# 18650_1S3P_Smart_VertCon.net
KiCad netlist of a schematic drawn in EAGLE
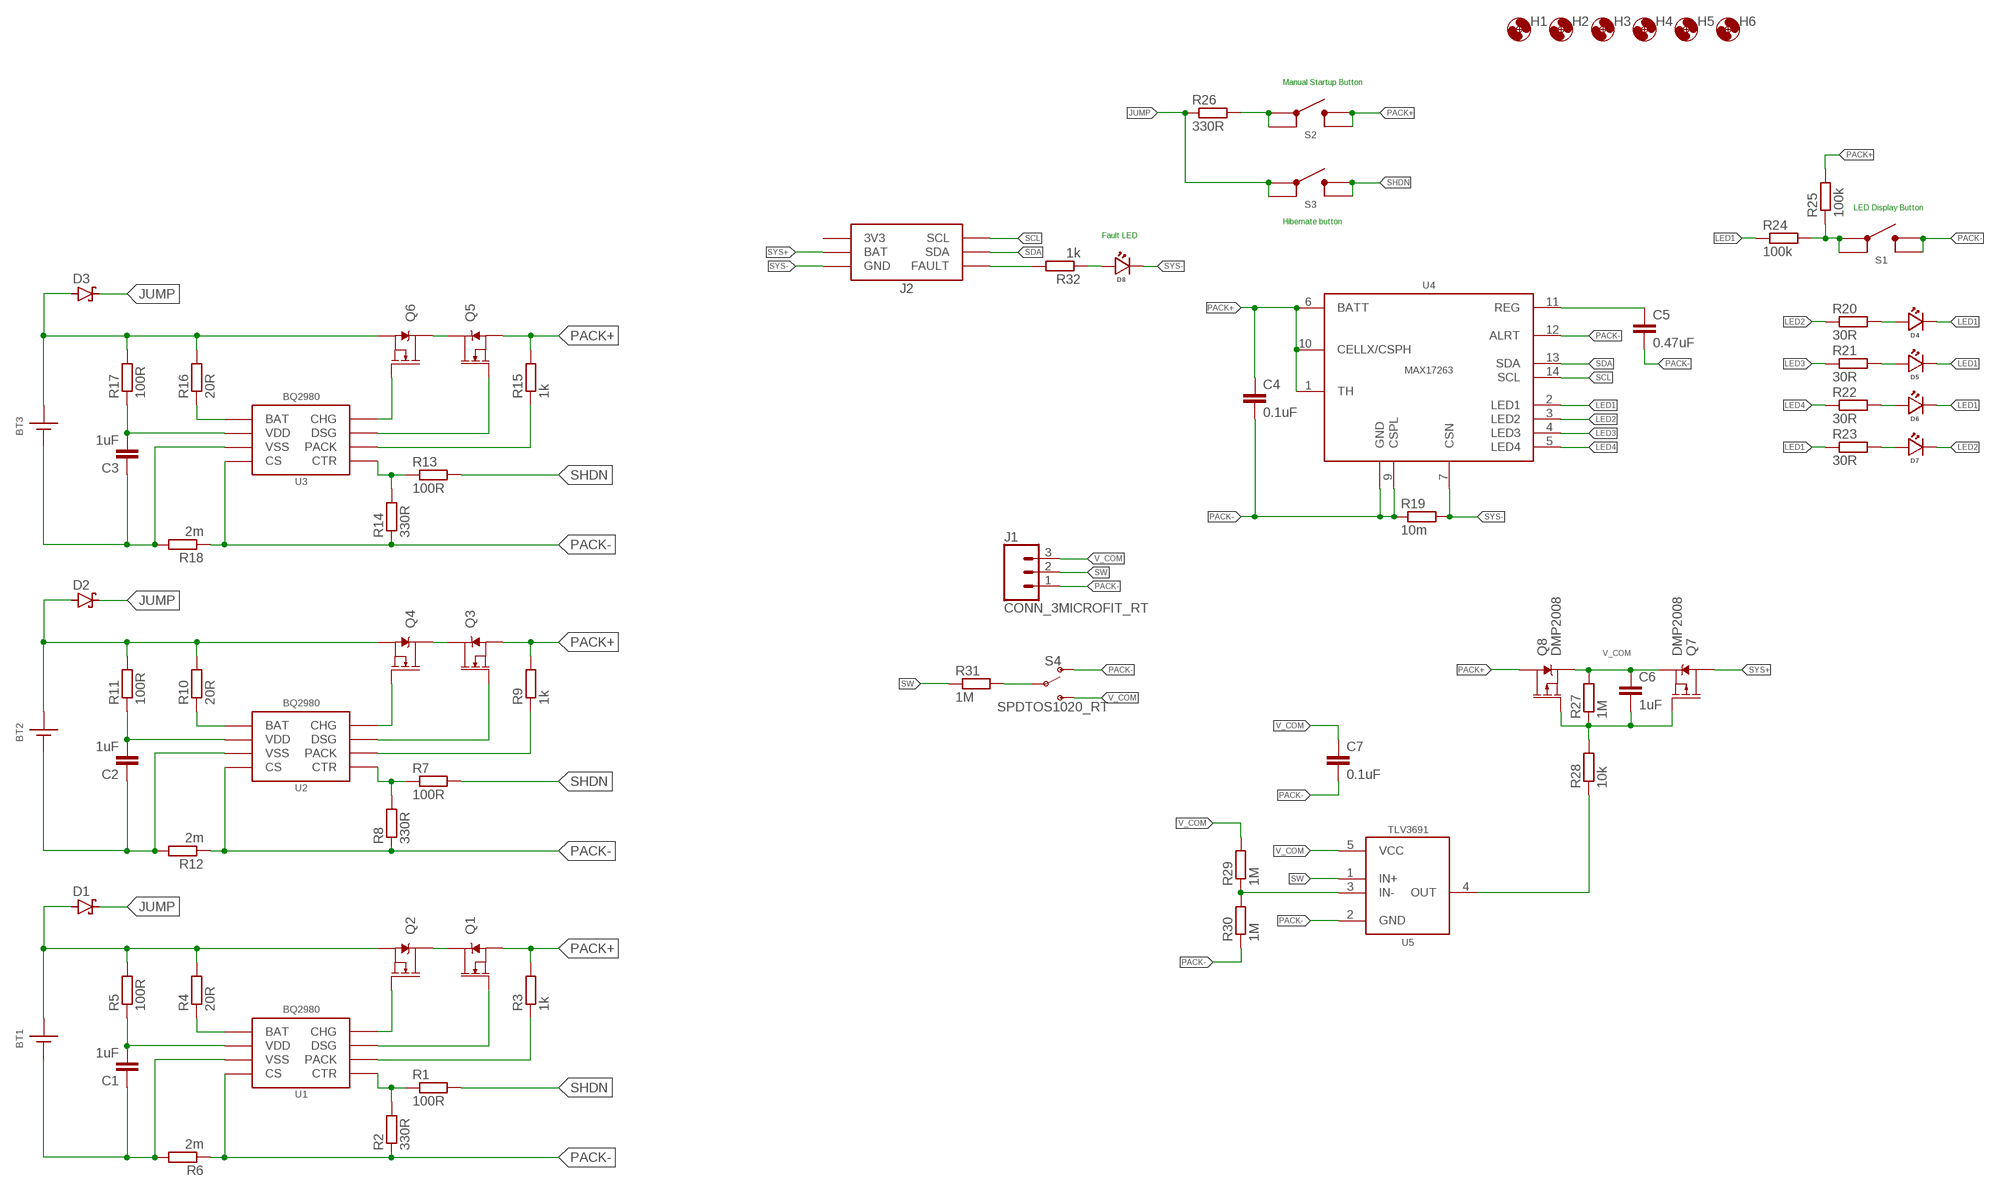
[diagram p0: schematic, sheet 1]

(export (version "E")
  (design (tool "Eeschema 10.0.6"))
  (components
    (comp (ref "BT1")
      (value "186501042")
      (footprint "eagle-import:BATT_1042P")
      (fields
        (field (name "MF") "Keystone")
        (field (name "MPN") "1042")
        (field (name "DIGIKEY") "36-1042-ND")
        (field (name "MPN_1") "1042")
      )
      (libsource (lib "eagle-import") (part "186501042"))
    )
    (comp (ref "BT2")
      (value "186501042")
      (footprint "eagle-import:BATT_1042P")
      (fields
        (field (name "MF") "Keystone")
        (field (name "MPN") "1042")
        (field (name "DIGIKEY") "36-1042-ND")
        (field (name "MPN_1") "1042")
      )
      (libsource (lib "eagle-import") (part "186501042"))
    )
    (comp (ref "BT3")
      (value "186501042")
      (footprint "eagle-import:BATT_1042P")
      (fields
        (field (name "MF") "Keystone")
        (field (name "MPN") "1042")
        (field (name "DIGIKEY") "36-1042-ND")
        (field (name "MPN_1") "1042")
      )
      (libsource (lib "eagle-import") (part "186501042"))
    )
    (comp (ref "C1")
      (value "1uF")
      (footprint "eagle-import:C0603")
      (fields (field (name "MF") "Yaiyo Yuden") (field (name "MPN") "TMK107B7105KA-T"))
      (libsource (lib "eagle-import") (part "C-EUC06031UF"))
    )
    (comp (ref "C2")
      (value "1uF")
      (footprint "eagle-import:C0603")
      (fields (field (name "MF") "Yaiyo Yuden") (field (name "MPN") "TMK107B7105KA-T"))
      (libsource (lib "eagle-import") (part "C-EUC06031UF"))
    )
    (comp (ref "C3")
      (value "1uF")
      (footprint "eagle-import:C0603")
      (fields (field (name "MF") "Yaiyo Yuden") (field (name "MPN") "TMK107B7105KA-T"))
      (libsource (lib "eagle-import") (part "C-EUC06031UF"))
    )
    (comp (ref "C4")
      (value "0.1uF")
      (footprint "eagle-import:C0603")
      (fields (field (name "MF") "Murata") (field (name "MPN") "GCM188R71E104KA57D"))
      (libsource (lib "eagle-import") (part "C-EUC06030.1UF"))
    )
    (comp (ref "C5")
      (value "0.47uF")
      (footprint "eagle-import:C0603")
      (fields (field (name "MF") "Samsung") (field (name "MPN") "CL10B474KA8NNNC"))
      (libsource (lib "eagle-import") (part "C-EUC06030.47UF"))
    )
    (comp (ref "C6")
      (value "1uF")
      (footprint "eagle-import:C0603")
      (fields (field (name "MF") "Yaiyo Yuden") (field (name "MPN") "TMK107B7105KA-T"))
      (libsource (lib "eagle-import") (part "C-EUC06031UF"))
    )
    (comp (ref "C7")
      (value "0.1uF")
      (footprint "eagle-import:C0603")
      (fields (field (name "MF") "Murata") (field (name "MPN") "GCM188R71E104KA57D"))
      (libsource (lib "eagle-import") (part "C-EUC06030.1UF"))
    )
    (comp (ref "D1")
      (value "DIODE_SCHOTTKYSOD-323")
      (footprint "eagle-import:SOD323-R")
      (fields
        (field (name "DIGIKEY") "BAT54WS-FDICT-ND")
        (field (name "MF") "Diodes Inc")
        (field (name "MPN") "BAT54WS-7-F")
      )
      (libsource (lib "eagle-import") (part "DIODE_SCHOTTKYSOD-323"))
    )
    (comp (ref "D2")
      (value "DIODE_SCHOTTKYSOD-323")
      (footprint "eagle-import:SOD323-R")
      (fields
        (field (name "DIGIKEY") "BAT54WS-FDICT-ND")
        (field (name "MF") "Diodes Inc")
        (field (name "MPN") "BAT54WS-7-F")
      )
      (libsource (lib "eagle-import") (part "DIODE_SCHOTTKYSOD-323"))
    )
    (comp (ref "D3")
      (value "DIODE_SCHOTTKYSOD-323")
      (footprint "eagle-import:SOD323-R")
      (fields
        (field (name "DIGIKEY") "BAT54WS-FDICT-ND")
        (field (name "MF") "Diodes Inc")
        (field (name "MPN") "BAT54WS-7-F")
      )
      (libsource (lib "eagle-import") (part "DIODE_SCHOTTKYSOD-323"))
    )
    (comp (ref "D4")
      (value "LED1206_BOTTOM")
      (footprint "eagle-import:LED_1206_BOTTOM")
      (fields (field (name "MF") "Lite-On") (field (name "MPN") "LTST-C230KGKT"))
      (libsource (lib "eagle-import") (part "LED1206_BOTTOM"))
    )
    (comp (ref "D5")
      (value "LED1206_BOTTOM")
      (footprint "eagle-import:LED_1206_BOTTOM")
      (fields (field (name "MF") "Lite-On") (field (name "MPN") "LTST-C230KGKT"))
      (libsource (lib "eagle-import") (part "LED1206_BOTTOM"))
    )
    (comp (ref "D6")
      (value "LED1206_BOTTOM")
      (footprint "eagle-import:LED_1206_BOTTOM")
      (fields (field (name "MF") "Lite-On") (field (name "MPN") "LTST-C230KGKT"))
      (libsource (lib "eagle-import") (part "LED1206_BOTTOM"))
    )
    (comp (ref "D7")
      (value "LED1206_BOTTOM")
      (footprint "eagle-import:LED_1206_BOTTOM")
      (fields (field (name "MF") "Lite-On") (field (name "MPN") "LTST-C230KGKT"))
      (libsource (lib "eagle-import") (part "LED1206_BOTTOM"))
    )
    (comp (ref "D8")
      (value "LED1206_BOTTOM")
      (footprint "eagle-import:LED_1206_BOTTOM")
      (fields (field (name "MF") "Lite-On") (field (name "MPN") "LTST-C230KRKT"))
      (libsource (lib "eagle-import") (part "LED1206_BOTTOM"))
    )
    (comp (ref "H1")
      (value "MOUNTING_HOLE4_NP")
      (footprint "eagle-import:4_40")
      (fields (field (name "MPN") "DNP"))
      (libsource (lib "eagle-import") (part "MOUNTING_HOLE4_NP"))
    )
    (comp (ref "H2")
      (value "MOUNTING_HOLE4_NP")
      (footprint "eagle-import:4_40")
      (fields (field (name "MPN") "DNP"))
      (libsource (lib "eagle-import") (part "MOUNTING_HOLE4_NP"))
    )
    (comp (ref "H3")
      (value "MOUNTING_HOLE4_NP")
      (footprint "eagle-import:4_40")
      (fields (field (name "MPN") "DNP"))
      (libsource (lib "eagle-import") (part "MOUNTING_HOLE4_NP"))
    )
    (comp (ref "H4")
      (value "MOUNTING_HOLE4_NP")
      (footprint "eagle-import:4_40")
      (fields (field (name "MPN") "DNP"))
      (libsource (lib "eagle-import") (part "MOUNTING_HOLE4_NP"))
    )
    (comp (ref "H5")
      (value "MOUNTING_HOLE4_NP")
      (footprint "eagle-import:4_40")
      (fields (field (name "MPN") "DNP"))
      (libsource (lib "eagle-import") (part "MOUNTING_HOLE4_NP"))
    )
    (comp (ref "H6")
      (value "MOUNTING_HOLE4_NP")
      (footprint "eagle-import:4_40")
      (fields (field (name "MPN") "DNP"))
      (libsource (lib "eagle-import") (part "MOUNTING_HOLE4_NP"))
    )
    (comp (ref "J1")
      (value "CONN_3MICROFIT_RT")
      (footprint "eagle-import:1X3_MICROFIT_RT")
      (fields (field (name "MF") "Molex") (field (name "MPN") "0436500300"))
      (libsource (lib "eagle-import") (part "CONN_3MICROFIT_RT"))
    )
    (comp (ref "J2")
      (value "GEMS_POWER_PLUGOUTPUT")
      (footprint "eagle-import:2X3_MICROFIT")
      (fields (field (name "MF") "Molex") (field (name "MPN") "0430450624"))
      (libsource (lib "eagle-import") (part "GEMS_POWER_PLUGOUTPUT"))
    )
    (comp (ref "Q1")
      (value "AON7522E")
      (footprint "eagle-import:DFN3X3A_8L_EP1_P")
      (fields (field (name "MF") "Alpha & Omega"))
      (libsource (lib "eagle-import") (part "MOSFET-NCH-AON7522E"))
    )
    (comp (ref "Q2")
      (value "AON7522E")
      (footprint "eagle-import:DFN3X3A_8L_EP1_P")
      (fields (field (name "MF") "Alpha & Omega"))
      (libsource (lib "eagle-import") (part "MOSFET-NCH-AON7522E"))
    )
    (comp (ref "Q3")
      (value "AON7522E")
      (footprint "eagle-import:DFN3X3A_8L_EP1_P")
      (fields (field (name "MF") "Alpha & Omega"))
      (libsource (lib "eagle-import") (part "MOSFET-NCH-AON7522E"))
    )
    (comp (ref "Q4")
      (value "AON7522E")
      (footprint "eagle-import:DFN3X3A_8L_EP1_P")
      (fields (field (name "MF") "Alpha & Omega"))
      (libsource (lib "eagle-import") (part "MOSFET-NCH-AON7522E"))
    )
    (comp (ref "Q5")
      (value "AON7522E")
      (footprint "eagle-import:DFN3X3A_8L_EP1_P")
      (fields (field (name "MF") "Alpha & Omega"))
      (libsource (lib "eagle-import") (part "MOSFET-NCH-AON7522E"))
    )
    (comp (ref "Q6")
      (value "AON7522E")
      (footprint "eagle-import:DFN3X3A_8L_EP1_P")
      (fields (field (name "MF") "Alpha & Omega"))
      (libsource (lib "eagle-import") (part "MOSFET-NCH-AON7522E"))
    )
    (comp (ref "Q7")
      (value "DMP2008")
      (footprint "eagle-import:POWERDI3333-8")
      (fields (field (name "MF") "Diodes Inc") (field (name "MPN") "DMP2008UFG-7"))
      (libsource (lib "eagle-import") (part "MOSFET-PCH-DMP2008"))
    )
    (comp (ref "Q8")
      (value "DMP2008")
      (footprint "eagle-import:POWERDI3333-8")
      (fields (field (name "MF") "Diodes Inc") (field (name "MPN") "DMP2008UFG-7"))
      (libsource (lib "eagle-import") (part "MOSFET-PCH-DMP2008"))
    )
    (comp (ref "R1")
      (value "100R")
      (footprint "eagle-import:R0603")
      (fields
        (field (name "MF") "Yageo")
        (field (name "MPN") "RC0603FR-07100RL")
        (field (name "VALUE_PART") "100")
      )
      (libsource (lib "eagle-import") (part "R-EU_R0603100"))
    )
    (comp (ref "R2")
      (value "330R")
      (footprint "eagle-import:R0603")
      (fields
        (field (name "MF") "Yageo")
        (field (name "MPN") "RC0603FR-07330RL")
        (field (name "VALUE_PART") "330")
      )
      (libsource (lib "eagle-import") (part "R-EU_R0603330"))
    )
    (comp (ref "R3")
      (value "1k")
      (footprint "eagle-import:R0603")
      (fields (field (name "MF") "Yageo") (field (name "MPN") "AC0603FR-071KL"))
      (libsource (lib "eagle-import") (part "R-EU_R06031K"))
    )
    (comp (ref "R4")
      (value "20R")
      (footprint "eagle-import:R0603")
      (fields
        (field (name "MF") "Yageo")
        (field (name "MPN") "RC0603FR-0720RL")
        (field (name "VALUE_PART") "20")
      )
      (libsource (lib "eagle-import") (part "R-EU_R060320"))
    )
    (comp (ref "R5")
      (value "100R")
      (footprint "eagle-import:R0603")
      (fields
        (field (name "MF") "Yageo")
        (field (name "MPN") "RC0603FR-07100RL")
        (field (name "VALUE_PART") "100")
      )
      (libsource (lib "eagle-import") (part "R-EU_R0603100"))
    )
    (comp (ref "R6")
      (value "2m")
      (footprint "eagle-import:R0805")
      (fields (field (name "MF") "Rohm") (field (name "MPN") "PMR10EZPFV2L00"))
      (libsource (lib "eagle-import") (part "R-EU_R08050.002"))
    )
    (comp (ref "R7")
      (value "100R")
      (footprint "eagle-import:R0603")
      (fields
        (field (name "MF") "Yageo")
        (field (name "MPN") "RC0603FR-07100RL")
        (field (name "VALUE_PART") "100")
      )
      (libsource (lib "eagle-import") (part "R-EU_R0603100"))
    )
    (comp (ref "R8")
      (value "330R")
      (footprint "eagle-import:R0603")
      (fields
        (field (name "MF") "Yageo")
        (field (name "MPN") "RC0603FR-07330RL")
        (field (name "VALUE_PART") "330")
      )
      (libsource (lib "eagle-import") (part "R-EU_R0603330"))
    )
    (comp (ref "R9")
      (value "1k")
      (footprint "eagle-import:R0603")
      (fields (field (name "MF") "Yageo") (field (name "MPN") "AC0603FR-071KL"))
      (libsource (lib "eagle-import") (part "R-EU_R06031K"))
    )
    (comp (ref "R10")
      (value "20R")
      (footprint "eagle-import:R0603")
      (fields
        (field (name "MF") "Yageo")
        (field (name "MPN") "RC0603FR-0720RL")
        (field (name "VALUE_PART") "20")
      )
      (libsource (lib "eagle-import") (part "R-EU_R060320"))
    )
    (comp (ref "R11")
      (value "100R")
      (footprint "eagle-import:R0603")
      (fields
        (field (name "MF") "Yageo")
        (field (name "MPN") "RC0603FR-07100RL")
        (field (name "VALUE_PART") "100")
      )
      (libsource (lib "eagle-import") (part "R-EU_R0603100"))
    )
    (comp (ref "R12")
      (value "2m")
      (footprint "eagle-import:R0805")
      (fields (field (name "MF") "Rohm") (field (name "MPN") "PMR10EZPFV2L00"))
      (libsource (lib "eagle-import") (part "R-EU_R08050.002"))
    )
    (comp (ref "R13")
      (value "100R")
      (footprint "eagle-import:R0603")
      (fields
        (field (name "MF") "Yageo")
        (field (name "MPN") "RC0603FR-07100RL")
        (field (name "VALUE_PART") "100")
      )
      (libsource (lib "eagle-import") (part "R-EU_R0603100"))
    )
    (comp (ref "R14")
      (value "330R")
      (footprint "eagle-import:R0603")
      (fields
        (field (name "MF") "Yageo")
        (field (name "MPN") "RC0603FR-07330RL")
        (field (name "VALUE_PART") "330")
      )
      (libsource (lib "eagle-import") (part "R-EU_R0603330"))
    )
    (comp (ref "R15")
      (value "1k")
      (footprint "eagle-import:R0603")
      (fields (field (name "MF") "Yageo") (field (name "MPN") "AC0603FR-071KL"))
      (libsource (lib "eagle-import") (part "R-EU_R06031K"))
    )
    (comp (ref "R16")
      (value "20R")
      (footprint "eagle-import:R0603")
      (fields
        (field (name "MF") "Yageo")
        (field (name "MPN") "RC0603FR-0720RL")
        (field (name "VALUE_PART") "20")
      )
      (libsource (lib "eagle-import") (part "R-EU_R060320"))
    )
    (comp (ref "R17")
      (value "100R")
      (footprint "eagle-import:R0603")
      (fields
        (field (name "MF") "Yageo")
        (field (name "MPN") "RC0603FR-07100RL")
        (field (name "VALUE_PART") "100")
      )
      (libsource (lib "eagle-import") (part "R-EU_R0603100"))
    )
    (comp (ref "R18")
      (value "2m")
      (footprint "eagle-import:R0805")
      (fields (field (name "MF") "Rohm") (field (name "MPN") "PMR10EZPFV2L00"))
      (libsource (lib "eagle-import") (part "R-EU_R08050.002"))
    )
    (comp (ref "R19")
      (value "10m")
      (footprint "eagle-import:R0805")
      (fields (field (name "MF") "Bourns") (field (name "MPN") "CRF0805-FZ-R010ELF"))
      (libsource (lib "eagle-import") (part "R-EU_R08050.01"))
    )
    (comp (ref "R20")
      (value "30R")
      (footprint "eagle-import:R0603")
      (fields
        (field (name "MF") "Yageo")
        (field (name "MPN") "RC0603FR-0730RL")
        (field (name "VALUE_PART") "30")
      )
      (libsource (lib "eagle-import") (part "R-EU_R060330"))
    )
    (comp (ref "R21")
      (value "30R")
      (footprint "eagle-import:R0603")
      (fields
        (field (name "MF") "Yageo")
        (field (name "MPN") "RC0603FR-0730RL")
        (field (name "VALUE_PART") "30")
      )
      (libsource (lib "eagle-import") (part "R-EU_R060330"))
    )
    (comp (ref "R22")
      (value "30R")
      (footprint "eagle-import:R0603")
      (fields
        (field (name "MF") "Yageo")
        (field (name "MPN") "RC0603FR-0730RL")
        (field (name "VALUE_PART") "30")
      )
      (libsource (lib "eagle-import") (part "R-EU_R060330"))
    )
    (comp (ref "R23")
      (value "30R")
      (footprint "eagle-import:R0603")
      (fields
        (field (name "MF") "Yageo")
        (field (name "MPN") "RC0603FR-0730RL")
        (field (name "VALUE_PART") "30")
      )
      (libsource (lib "eagle-import") (part "R-EU_R060330"))
    )
    (comp (ref "R24")
      (value "100k")
      (footprint "eagle-import:R0603")
      (fields (field (name "MF") "Yageo") (field (name "MPN") "RC0603FR-07100KL"))
      (libsource (lib "eagle-import") (part "R-EU_R0603100K"))
    )
    (comp (ref "R25")
      (value "100k")
      (footprint "eagle-import:R0603")
      (fields (field (name "MF") "Yageo") (field (name "MPN") "RC0603FR-07100KL"))
      (libsource (lib "eagle-import") (part "R-EU_R0603100K"))
    )
    (comp (ref "R26")
      (value "330R")
      (footprint "eagle-import:R0603")
      (fields
        (field (name "MF") "Yageo")
        (field (name "MPN") "RC0603FR-07330RL")
        (field (name "VALUE_PART") "330")
      )
      (libsource (lib "eagle-import") (part "R-EU_R0603330"))
    )
    (comp (ref "R27")
      (value "1M")
      (footprint "eagle-import:R0603")
      (fields (field (name "MF") "Panasonic") (field (name "MPN") "ERJ-3EKF1004V"))
      (libsource (lib "eagle-import") (part "R-EU_R06031M"))
    )
    (comp (ref "R28")
      (value "10k")
      (footprint "eagle-import:R0603")
      (fields (field (name "MF") "Yageo") (field (name "MPN") "RC0603FR-0710KL"))
      (libsource (lib "eagle-import") (part "R-EU_R060310K"))
    )
    (comp (ref "R29")
      (value "1M")
      (footprint "eagle-import:R0603")
      (fields (field (name "MF") "Panasonic") (field (name "MPN") "ERJ-3EKF1004V"))
      (libsource (lib "eagle-import") (part "R-EU_R06031M"))
    )
    (comp (ref "R30")
      (value "1M")
      (footprint "eagle-import:R0603")
      (fields (field (name "MF") "Panasonic") (field (name "MPN") "ERJ-3EKF1004V"))
      (libsource (lib "eagle-import") (part "R-EU_R06031M"))
    )
    (comp (ref "R31")
      (value "1M")
      (footprint "eagle-import:R0603")
      (fields (field (name "MF") "Panasonic") (field (name "MPN") "ERJ-3EKF1004V"))
      (libsource (lib "eagle-import") (part "R-EU_R06031M"))
    )
    (comp (ref "R32")
      (value "1k")
      (footprint "eagle-import:R0603")
      (fields (field (name "MF") "Yageo") (field (name "MPN") "AC0603FR-071KL"))
      (libsource (lib "eagle-import") (part "R-EU_R06031K"))
    )
    (comp (ref "S1")
      (value "BUTTON6X6_TH")
      (footprint "eagle-import:SWITCH_6MM_TH")
      (fields (field (name "MF") "TE Connectivity") (field (name "MPN") "1825910-6"))
      (libsource (lib "eagle-import") (part "BUTTON6X6_TH"))
    )
    (comp (ref "S2")
      (value "BUTTON6X6_TH")
      (footprint "eagle-import:SWITCH_6MM_TH")
      (fields (field (name "MF") "TE Connectivity") (field (name "MPN") "1825910-6"))
      (libsource (lib "eagle-import") (part "BUTTON6X6_TH"))
    )
    (comp (ref "S3")
      (value "BUTTON6X6_TH")
      (footprint "eagle-import:SWITCH_6MM_TH")
      (fields (field (name "MF") "TE Connectivity") (field (name "MPN") "1825910-6"))
      (libsource (lib "eagle-import") (part "BUTTON6X6_TH"))
    )
    (comp (ref "S4")
      (value "SPDTOS1020_RT")
      (footprint "eagle-import:OS102011MA1QN1")
      (fields (field (name "MF") "C&K") (field (name "MPN") "OS102011MA1QN1"))
      (libsource (lib "eagle-import") (part "SPDTOS1020_RT"))
    )
    (comp (ref "U1")
      (value "BQ2980RUG")
      (footprint "eagle-import:RUG_S-PQFP-N8")
      (fields (field (name "MF") "TI") (field (name "MPN") "BQ298000RUGT"))
      (libsource (lib "eagle-import") (part "BQ2980RUG"))
    )
    (comp (ref "U2")
      (value "BQ2980RUG")
      (footprint "eagle-import:RUG_S-PQFP-N8")
      (fields (field (name "MF") "TI") (field (name "MPN") "BQ298000RUGT"))
      (libsource (lib "eagle-import") (part "BQ2980RUG"))
    )
    (comp (ref "U3")
      (value "BQ2980RUG")
      (footprint "eagle-import:RUG_S-PQFP-N8")
      (fields (field (name "MF") "TI") (field (name "MPN") "BQ298000RUGT"))
      (libsource (lib "eagle-import") (part "BQ2980RUG"))
    )
    (comp (ref "U4")
      (value "MAX17263")
      (footprint "eagle-import:DFN_14_3X3")
      (fields (field (name "MF") "Maxim") (field (name "MPN") "MAX17263LETD+T"))
      (libsource (lib "eagle-import") (part "MAX17263"))
    )
    (comp (ref "U5")
      (value "TLV3691DCK")
      (footprint "eagle-import:DCK_R-PDSO-G5")
      (fields (field (name "MF") "TI") (field (name "MPN") "TLV3691IDCKR"))
      (libsource (lib "eagle-import") (part "TLV3691DCK"))
    )
  )
  (nets
    (net (code "1") (name "/3V3") (class "Default")
      (node (ref "J2") (pin "5") (pinfunction "3V3_5") (pintype "power_in"))
    )
    (net (code "2") (name "JUMP") (class "Default")
      (node (ref "D1") (pin "C") (pinfunction "C_C") (pintype "passive"))
      (node (ref "D2") (pin "C") (pinfunction "C_C") (pintype "passive"))
      (node (ref "D3") (pin "C") (pinfunction "C_C") (pintype "passive"))
      (node (ref "R26") (pin "1") (pinfunction "1_1") (pintype "passive"))
      (node (ref "S3") (pin "1") (pinfunction "1_1") (pintype "bidirectional"))
      (node (ref "S3") (pin "2") (pinfunction "2_2") (pintype "bidirectional"))
    )
    (net (code "3") (name "LED1") (class "Default")
      (node (ref "D4") (pin "CATHODE") (pinfunction "CATHODE_CATHODE") (pintype "power_in"))
      (node (ref "D5") (pin "CATHODE") (pinfunction "CATHODE_CATHODE") (pintype "power_in"))
      (node (ref "D6") (pin "CATHODE") (pinfunction "CATHODE_CATHODE") (pintype "power_in"))
      (node (ref "R23") (pin "1") (pinfunction "1_1") (pintype "passive"))
      (node (ref "R24") (pin "1") (pinfunction "1_1") (pintype "passive"))
      (node (ref "U4") (pin "2") (pinfunction "LED1_2") (pintype "bidirectional"))
    )
    (net (code "4") (name "LED2") (class "Default")
      (node (ref "D7") (pin "CATHODE") (pinfunction "CATHODE_CATHODE") (pintype "power_in"))
      (node (ref "R20") (pin "1") (pinfunction "1_1") (pintype "passive"))
      (node (ref "U4") (pin "3") (pinfunction "LED2_3") (pintype "bidirectional"))
    )
    (net (code "5") (name "LED3") (class "Default")
      (node (ref "R21") (pin "1") (pinfunction "1_1") (pintype "passive"))
      (node (ref "U4") (pin "4") (pinfunction "LED3_4") (pintype "bidirectional"))
    )
    (net (code "6") (name "LED4") (class "Default")
      (node (ref "R22") (pin "1") (pinfunction "1_1") (pintype "passive"))
      (node (ref "U4") (pin "5") (pinfunction "LED4_5") (pintype "bidirectional"))
    )
    (net (code "7") (name "Net-(BT1-+)") (class "Default")
      (node (ref "BT1") (pin "BATT+") (pinfunction "+_BATT+") (pintype "power_in"))
      (node (ref "D1") (pin "A") (pinfunction "A_A") (pintype "passive"))
      (node (ref "Q2") (pin "S@1") (pinfunction "S_S@1") (pintype "bidirectional"))
      (node (ref "Q2") (pin "S@2") (pinfunction "S_S@2") (pintype "bidirectional"))
      (node (ref "Q2") (pin "S@3") (pinfunction "S_S@3") (pintype "bidirectional"))
      (node (ref "R4") (pin "2") (pinfunction "2_2") (pintype "passive"))
      (node (ref "R5") (pin "2") (pinfunction "2_2") (pintype "passive"))
    )
    (net (code "8") (name "Net-(BT1--)") (class "Default")
      (node (ref "BT1") (pin "BATT-") (pinfunction "-_BATT-") (pintype "power_in"))
      (node (ref "C1") (pin "1") (pinfunction "1_1") (pintype "passive"))
      (node (ref "R6") (pin "2") (pinfunction "2_2") (pintype "passive"))
      (node (ref "U1") (pin "3") (pinfunction "VSS_3") (pintype "power_in"))
    )
    (net (code "9") (name "Net-(BT2-+)") (class "Default")
      (node (ref "BT2") (pin "BATT+") (pinfunction "+_BATT+") (pintype "power_in"))
      (node (ref "D2") (pin "A") (pinfunction "A_A") (pintype "passive"))
      (node (ref "Q4") (pin "S@1") (pinfunction "S_S@1") (pintype "bidirectional"))
      (node (ref "Q4") (pin "S@2") (pinfunction "S_S@2") (pintype "bidirectional"))
      (node (ref "Q4") (pin "S@3") (pinfunction "S_S@3") (pintype "bidirectional"))
      (node (ref "R10") (pin "2") (pinfunction "2_2") (pintype "passive"))
      (node (ref "R11") (pin "2") (pinfunction "2_2") (pintype "passive"))
    )
    (net (code "10") (name "Net-(BT2--)") (class "Default")
      (node (ref "BT2") (pin "BATT-") (pinfunction "-_BATT-") (pintype "power_in"))
      (node (ref "C2") (pin "1") (pinfunction "1_1") (pintype "passive"))
      (node (ref "R12") (pin "2") (pinfunction "2_2") (pintype "passive"))
      (node (ref "U2") (pin "3") (pinfunction "VSS_3") (pintype "power_in"))
    )
    (net (code "11") (name "Net-(BT3-+)") (class "Default")
      (node (ref "BT3") (pin "BATT+") (pinfunction "+_BATT+") (pintype "power_in"))
      (node (ref "D3") (pin "A") (pinfunction "A_A") (pintype "passive"))
      (node (ref "Q6") (pin "S@1") (pinfunction "S_S@1") (pintype "bidirectional"))
      (node (ref "Q6") (pin "S@2") (pinfunction "S_S@2") (pintype "bidirectional"))
      (node (ref "Q6") (pin "S@3") (pinfunction "S_S@3") (pintype "bidirectional"))
      (node (ref "R16") (pin "2") (pinfunction "2_2") (pintype "passive"))
      (node (ref "R17") (pin "2") (pinfunction "2_2") (pintype "passive"))
    )
    (net (code "12") (name "Net-(BT3--)") (class "Default")
      (node (ref "BT3") (pin "BATT-") (pinfunction "-_BATT-") (pintype "power_in"))
      (node (ref "C3") (pin "1") (pinfunction "1_1") (pintype "passive"))
      (node (ref "R18") (pin "2") (pinfunction "2_2") (pintype "passive"))
      (node (ref "U3") (pin "3") (pinfunction "VSS_3") (pintype "power_in"))
    )
    (net (code "13") (name "Net-(D4-PadANODE)") (class "Default")
      (node (ref "D4") (pin "ANODE") (pinfunction "ANODE_ANODE") (pintype "power_in"))
      (node (ref "R20") (pin "2") (pinfunction "2_2") (pintype "passive"))
    )
    (net (code "14") (name "Net-(D5-PadANODE)") (class "Default")
      (node (ref "D5") (pin "ANODE") (pinfunction "ANODE_ANODE") (pintype "power_in"))
      (node (ref "R21") (pin "2") (pinfunction "2_2") (pintype "passive"))
    )
    (net (code "15") (name "Net-(D6-PadANODE)") (class "Default")
      (node (ref "D6") (pin "ANODE") (pinfunction "ANODE_ANODE") (pintype "power_in"))
      (node (ref "R22") (pin "2") (pinfunction "2_2") (pintype "passive"))
    )
    (net (code "16") (name "Net-(D7-PadANODE)") (class "Default")
      (node (ref "D7") (pin "ANODE") (pinfunction "ANODE_ANODE") (pintype "power_in"))
      (node (ref "R23") (pin "2") (pinfunction "2_2") (pintype "passive"))
    )
    (net (code "17") (name "Net-(D8-PadANODE)") (class "Default")
      (node (ref "D8") (pin "ANODE") (pinfunction "ANODE_ANODE") (pintype "power_in"))
      (node (ref "R32") (pin "1") (pinfunction "1_1") (pintype "passive"))
    )
    (net (code "18") (name "Net-(J2-FAULT)") (class "Default")
      (node (ref "J2") (pin "1") (pinfunction "FAULT_1") (pintype "bidirectional"))
      (node (ref "R32") (pin "2") (pinfunction "2_2") (pintype "passive"))
    )
    (net (code "19") (name "Net-(Q1-PadD)") (class "Default")
      (node (ref "Q1") (pin "D") (pinfunction "D_D") (pintype "bidirectional"))
      (node (ref "Q2") (pin "D") (pinfunction "D_D") (pintype "bidirectional"))
    )
    (net (code "20") (name "Net-(Q3-PadD)") (class "Default")
      (node (ref "Q3") (pin "D") (pinfunction "D_D") (pintype "bidirectional"))
      (node (ref "Q4") (pin "D") (pinfunction "D_D") (pintype "bidirectional"))
    )
    (net (code "21") (name "Net-(Q5-PadD)") (class "Default")
      (node (ref "Q5") (pin "D") (pinfunction "D_D") (pintype "bidirectional"))
      (node (ref "Q6") (pin "D") (pinfunction "D_D") (pintype "bidirectional"))
    )
    (net (code "22") (name "Net-(Q7-G)") (class "Default")
      (node (ref "C6") (pin "2") (pinfunction "2_2") (pintype "passive"))
      (node (ref "Q7") (pin "4") (pinfunction "G_4") (pintype "bidirectional"))
      (node (ref "Q8") (pin "4") (pinfunction "G_4") (pintype "bidirectional"))
      (node (ref "R27") (pin "1") (pinfunction "1_1") (pintype "passive"))
      (node (ref "R28") (pin "2") (pinfunction "2_2") (pintype "passive"))
    )
    (net (code "23") (name "Net-(R24-Pad2)") (class "Default")
      (node (ref "R24") (pin "2") (pinfunction "2_2") (pintype "passive"))
      (node (ref "R25") (pin "1") (pinfunction "1_1") (pintype "passive"))
      (node (ref "S1") (pin "1") (pinfunction "1_1") (pintype "bidirectional"))
      (node (ref "S1") (pin "2") (pinfunction "2_2") (pintype "bidirectional"))
    )
    (net (code "24") (name "Net-(R26-Pad2)") (class "Default")
      (node (ref "R26") (pin "2") (pinfunction "2_2") (pintype "passive"))
      (node (ref "S2") (pin "1") (pinfunction "1_1") (pintype "bidirectional"))
      (node (ref "S2") (pin "2") (pinfunction "2_2") (pintype "bidirectional"))
    )
    (net (code "25") (name "Net-(S4-P)") (class "Default")
      (node (ref "R31") (pin "2") (pinfunction "2_2") (pintype "passive"))
      (node (ref "S4") (pin "2") (pinfunction "P_2") (pintype "passive"))
    )
    (net (code "26") (name "Net-(U1-BAT)") (class "Default")
      (node (ref "R4") (pin "1") (pinfunction "1_1") (pintype "passive"))
      (node (ref "U1") (pin "1") (pinfunction "BAT_1") (pintype "power_in"))
    )
    (net (code "27") (name "Net-(U1-CHG)") (class "Default")
      (node (ref "Q2") (pin "G") (pinfunction "G_G") (pintype "bidirectional"))
      (node (ref "U1") (pin "8") (pinfunction "CHG_8") (pintype "output"))
    )
    (net (code "28") (name "Net-(U1-CTR)") (class "Default")
      (node (ref "R1") (pin "1") (pinfunction "1_1") (pintype "passive"))
      (node (ref "R2") (pin "2") (pinfunction "2_2") (pintype "passive"))
      (node (ref "U1") (pin "5") (pinfunction "CTR_5") (pintype "input"))
    )
    (net (code "29") (name "Net-(U1-DSG)") (class "Default")
      (node (ref "Q1") (pin "G") (pinfunction "G_G") (pintype "bidirectional"))
      (node (ref "U1") (pin "7") (pinfunction "DSG_7") (pintype "output"))
    )
    (net (code "30") (name "Net-(U1-PACK)") (class "Default")
      (node (ref "R3") (pin "1") (pinfunction "1_1") (pintype "passive"))
      (node (ref "U1") (pin "6") (pinfunction "PACK_6") (pintype "input"))
    )
    (net (code "31") (name "Net-(U1-VDD)") (class "Default")
      (node (ref "C1") (pin "2") (pinfunction "2_2") (pintype "passive"))
      (node (ref "R5") (pin "1") (pinfunction "1_1") (pintype "passive"))
      (node (ref "U1") (pin "2") (pinfunction "VDD_2") (pintype "power_in"))
    )
    (net (code "32") (name "Net-(U2-BAT)") (class "Default")
      (node (ref "R10") (pin "1") (pinfunction "1_1") (pintype "passive"))
      (node (ref "U2") (pin "1") (pinfunction "BAT_1") (pintype "power_in"))
    )
    (net (code "33") (name "Net-(U2-CHG)") (class "Default")
      (node (ref "Q4") (pin "G") (pinfunction "G_G") (pintype "bidirectional"))
      (node (ref "U2") (pin "8") (pinfunction "CHG_8") (pintype "output"))
    )
    (net (code "34") (name "Net-(U2-CTR)") (class "Default")
      (node (ref "R7") (pin "1") (pinfunction "1_1") (pintype "passive"))
      (node (ref "R8") (pin "2") (pinfunction "2_2") (pintype "passive"))
      (node (ref "U2") (pin "5") (pinfunction "CTR_5") (pintype "input"))
    )
    (net (code "35") (name "Net-(U2-DSG)") (class "Default")
      (node (ref "Q3") (pin "G") (pinfunction "G_G") (pintype "bidirectional"))
      (node (ref "U2") (pin "7") (pinfunction "DSG_7") (pintype "output"))
    )
    (net (code "36") (name "Net-(U2-PACK)") (class "Default")
      (node (ref "R9") (pin "1") (pinfunction "1_1") (pintype "passive"))
      (node (ref "U2") (pin "6") (pinfunction "PACK_6") (pintype "input"))
    )
    (net (code "37") (name "Net-(U2-VDD)") (class "Default")
      (node (ref "C2") (pin "2") (pinfunction "2_2") (pintype "passive"))
      (node (ref "R11") (pin "1") (pinfunction "1_1") (pintype "passive"))
      (node (ref "U2") (pin "2") (pinfunction "VDD_2") (pintype "power_in"))
    )
    (net (code "38") (name "Net-(U3-BAT)") (class "Default")
      (node (ref "R16") (pin "1") (pinfunction "1_1") (pintype "passive"))
      (node (ref "U3") (pin "1") (pinfunction "BAT_1") (pintype "power_in"))
    )
    (net (code "39") (name "Net-(U3-CHG)") (class "Default")
      (node (ref "Q6") (pin "G") (pinfunction "G_G") (pintype "bidirectional"))
      (node (ref "U3") (pin "8") (pinfunction "CHG_8") (pintype "output"))
    )
    (net (code "40") (name "Net-(U3-CTR)") (class "Default")
      (node (ref "R13") (pin "1") (pinfunction "1_1") (pintype "passive"))
      (node (ref "R14") (pin "2") (pinfunction "2_2") (pintype "passive"))
      (node (ref "U3") (pin "5") (pinfunction "CTR_5") (pintype "input"))
    )
    (net (code "41") (name "Net-(U3-DSG)") (class "Default")
      (node (ref "Q5") (pin "G") (pinfunction "G_G") (pintype "bidirectional"))
      (node (ref "U3") (pin "7") (pinfunction "DSG_7") (pintype "output"))
    )
    (net (code "42") (name "Net-(U3-PACK)") (class "Default")
      (node (ref "R15") (pin "1") (pinfunction "1_1") (pintype "passive"))
      (node (ref "U3") (pin "6") (pinfunction "PACK_6") (pintype "input"))
    )
    (net (code "43") (name "Net-(U3-VDD)") (class "Default")
      (node (ref "C3") (pin "2") (pinfunction "2_2") (pintype "passive"))
      (node (ref "R17") (pin "1") (pinfunction "1_1") (pintype "passive"))
      (node (ref "U3") (pin "2") (pinfunction "VDD_2") (pintype "power_in"))
    )
    (net (code "44") (name "Net-(U4-REG)") (class "Default")
      (node (ref "C5") (pin "1") (pinfunction "1_1") (pintype "passive"))
      (node (ref "U4") (pin "11") (pinfunction "REG_11") (pintype "power_in"))
    )
    (net (code "45") (name "Net-(U5-IN-)") (class "Default")
      (node (ref "R29") (pin "1") (pinfunction "1_1") (pintype "passive"))
      (node (ref "R30") (pin "2") (pinfunction "2_2") (pintype "passive"))
      (node (ref "U5") (pin "3") (pinfunction "IN-_3") (pintype "input"))
    )
    (net (code "46") (name "Net-(U5-OUT)") (class "Default")
      (node (ref "R28") (pin "1") (pinfunction "1_1") (pintype "passive"))
      (node (ref "U5") (pin "4") (pinfunction "OUT_4") (pintype "output"))
    )
    (net (code "47") (name "PACK+") (class "Default")
      (node (ref "C4") (pin "1") (pinfunction "1_1") (pintype "passive"))
      (node (ref "Q1") (pin "S@1") (pinfunction "S_S@1") (pintype "bidirectional"))
      (node (ref "Q1") (pin "S@2") (pinfunction "S_S@2") (pintype "bidirectional"))
      (node (ref "Q1") (pin "S@3") (pinfunction "S_S@3") (pintype "bidirectional"))
      (node (ref "Q3") (pin "S@1") (pinfunction "S_S@1") (pintype "bidirectional"))
      (node (ref "Q3") (pin "S@2") (pinfunction "S_S@2") (pintype "bidirectional"))
      (node (ref "Q3") (pin "S@3") (pinfunction "S_S@3") (pintype "bidirectional"))
      (node (ref "Q5") (pin "S@1") (pinfunction "S_S@1") (pintype "bidirectional"))
      (node (ref "Q5") (pin "S@2") (pinfunction "S_S@2") (pintype "bidirectional"))
      (node (ref "Q5") (pin "S@3") (pinfunction "S_S@3") (pintype "bidirectional"))
      (node (ref "Q8") (pin "EP@1") (pinfunction "D_EP@1") (pintype "bidirectional"))
      (node (ref "Q8") (pin "EP@2") (pinfunction "D_EP@2") (pintype "bidirectional"))
      (node (ref "Q8") (pin "EP@3") (pinfunction "D_EP@3") (pintype "bidirectional"))
      (node (ref "Q8") (pin "EP@4") (pinfunction "D_EP@4") (pintype "bidirectional"))
      (node (ref "Q8") (pin "EP@5") (pinfunction "D_EP@5") (pintype "bidirectional"))
      (node (ref "R15") (pin "2") (pinfunction "2_2") (pintype "passive"))
      (node (ref "R25") (pin "2") (pinfunction "2_2") (pintype "passive"))
      (node (ref "R3") (pin "2") (pinfunction "2_2") (pintype "passive"))
      (node (ref "R9") (pin "2") (pinfunction "2_2") (pintype "passive"))
      (node (ref "S2") (pin "3") (pinfunction "3_3") (pintype "bidirectional"))
      (node (ref "S2") (pin "4") (pinfunction "4_4") (pintype "bidirectional"))
      (node (ref "U4") (pin "1") (pinfunction "TH_1") (pintype "input"))
      (node (ref "U4") (pin "10") (pinfunction "CELLX/CSPH_10") (pintype "input"))
      (node (ref "U4") (pin "6") (pinfunction "BATT_6") (pintype "power_in"))
    )
    (net (code "48") (name "PACK-") (class "Default")
      (node (ref "C4") (pin "2") (pinfunction "2_2") (pintype "passive"))
      (node (ref "C5") (pin "2") (pinfunction "2_2") (pintype "passive"))
      (node (ref "C7") (pin "2") (pinfunction "2_2") (pintype "passive"))
      (node (ref "J1") (pin "1") (pinfunction "1_1") (pintype "passive"))
      (node (ref "R12") (pin "1") (pinfunction "1_1") (pintype "passive"))
      (node (ref "R14") (pin "1") (pinfunction "1_1") (pintype "passive"))
      (node (ref "R18") (pin "1") (pinfunction "1_1") (pintype "passive"))
      (node (ref "R19") (pin "1") (pinfunction "1_1") (pintype "passive"))
      (node (ref "R2") (pin "1") (pinfunction "1_1") (pintype "passive"))
      (node (ref "R30") (pin "1") (pinfunction "1_1") (pintype "passive"))
      (node (ref "R6") (pin "1") (pinfunction "1_1") (pintype "passive"))
      (node (ref "R8") (pin "1") (pinfunction "1_1") (pintype "passive"))
      (node (ref "S1") (pin "3") (pinfunction "3_3") (pintype "bidirectional"))
      (node (ref "S1") (pin "4") (pinfunction "4_4") (pintype "bidirectional"))
      (node (ref "S4") (pin "1") (pinfunction "O_1") (pintype "passive"))
      (node (ref "U1") (pin "4") (pinfunction "CS_4") (pintype "input"))
      (node (ref "U2") (pin "4") (pinfunction "CS_4") (pintype "input"))
      (node (ref "U3") (pin "4") (pinfunction "CS_4") (pintype "input"))
      (node (ref "U4") (pin "12") (pinfunction "ALRT_12") (pintype "open_collector"))
      (node (ref "U4") (pin "8") (pinfunction "GND_8") (pintype "power_in"))
      (node (ref "U4") (pin "9") (pinfunction "CSPL_9") (pintype "input"))
      (node (ref "U4") (pin "EP") (pinfunction "GND_EP") (pintype "power_in"))
      (node (ref "U5") (pin "2") (pinfunction "GND_2") (pintype "power_in"))
    )
    (net (code "49") (name "SCL") (class "Default")
      (node (ref "J2") (pin "4") (pinfunction "SCL_4") (pintype "bidirectional"))
      (node (ref "U4") (pin "14") (pinfunction "SCL_14") (pintype "input"))
    )
    (net (code "50") (name "SDA") (class "Default")
      (node (ref "J2") (pin "6") (pinfunction "SDA_6") (pintype "bidirectional"))
      (node (ref "U4") (pin "13") (pinfunction "SDA_13") (pintype "bidirectional"))
    )
    (net (code "51") (name "SHDN") (class "Default")
      (node (ref "R1") (pin "2") (pinfunction "2_2") (pintype "passive"))
      (node (ref "R13") (pin "2") (pinfunction "2_2") (pintype "passive"))
      (node (ref "R7") (pin "2") (pinfunction "2_2") (pintype "passive"))
      (node (ref "S3") (pin "3") (pinfunction "3_3") (pintype "bidirectional"))
      (node (ref "S3") (pin "4") (pinfunction "4_4") (pintype "bidirectional"))
    )
    (net (code "52") (name "SW") (class "Default")
      (node (ref "J1") (pin "2") (pinfunction "2_2") (pintype "passive"))
      (node (ref "R31") (pin "1") (pinfunction "1_1") (pintype "passive"))
      (node (ref "U5") (pin "1") (pinfunction "IN+_1") (pintype "input"))
    )
    (net (code "53") (name "SYS+") (class "Default")
      (node (ref "J2") (pin "3") (pinfunction "BAT_3") (pintype "power_in"))
      (node (ref "Q7") (pin "EP@1") (pinfunction "D_EP@1") (pintype "bidirectional"))
      (node (ref "Q7") (pin "EP@2") (pinfunction "D_EP@2") (pintype "bidirectional"))
      (node (ref "Q7") (pin "EP@3") (pinfunction "D_EP@3") (pintype "bidirectional"))
      (node (ref "Q7") (pin "EP@4") (pinfunction "D_EP@4") (pintype "bidirectional"))
      (node (ref "Q7") (pin "EP@5") (pinfunction "D_EP@5") (pintype "bidirectional"))
    )
    (net (code "54") (name "SYS-") (class "Default")
      (node (ref "D8") (pin "CATHODE") (pinfunction "CATHODE_CATHODE") (pintype "power_in"))
      (node (ref "J2") (pin "2") (pinfunction "GND_2") (pintype "power_in"))
      (node (ref "R19") (pin "2") (pinfunction "2_2") (pintype "passive"))
      (node (ref "U4") (pin "7") (pinfunction "CSN_7") (pintype "input"))
    )
    (net (code "55") (name "V_COM") (class "Default")
      (node (ref "C6") (pin "1") (pinfunction "1_1") (pintype "passive"))
      (node (ref "C7") (pin "1") (pinfunction "1_1") (pintype "passive"))
      (node (ref "J1") (pin "3") (pinfunction "3_3") (pintype "passive"))
      (node (ref "Q7") (pin "1") (pinfunction "S_1") (pintype "bidirectional"))
      (node (ref "Q7") (pin "2") (pinfunction "S_2") (pintype "bidirectional"))
      (node (ref "Q7") (pin "3") (pinfunction "S_3") (pintype "bidirectional"))
      (node (ref "Q8") (pin "1") (pinfunction "S_1") (pintype "bidirectional"))
      (node (ref "Q8") (pin "2") (pinfunction "S_2") (pintype "bidirectional"))
      (node (ref "Q8") (pin "3") (pinfunction "S_3") (pintype "bidirectional"))
      (node (ref "R27") (pin "2") (pinfunction "2_2") (pintype "passive"))
      (node (ref "R29") (pin "2") (pinfunction "2_2") (pintype "passive"))
      (node (ref "S4") (pin "3") (pinfunction "S_3") (pintype "passive"))
      (node (ref "U5") (pin "5") (pinfunction "VCC_5") (pintype "power_in"))
    )
  )
)
